# power.net
KiCad netlist of a schematic drawn in EAGLE
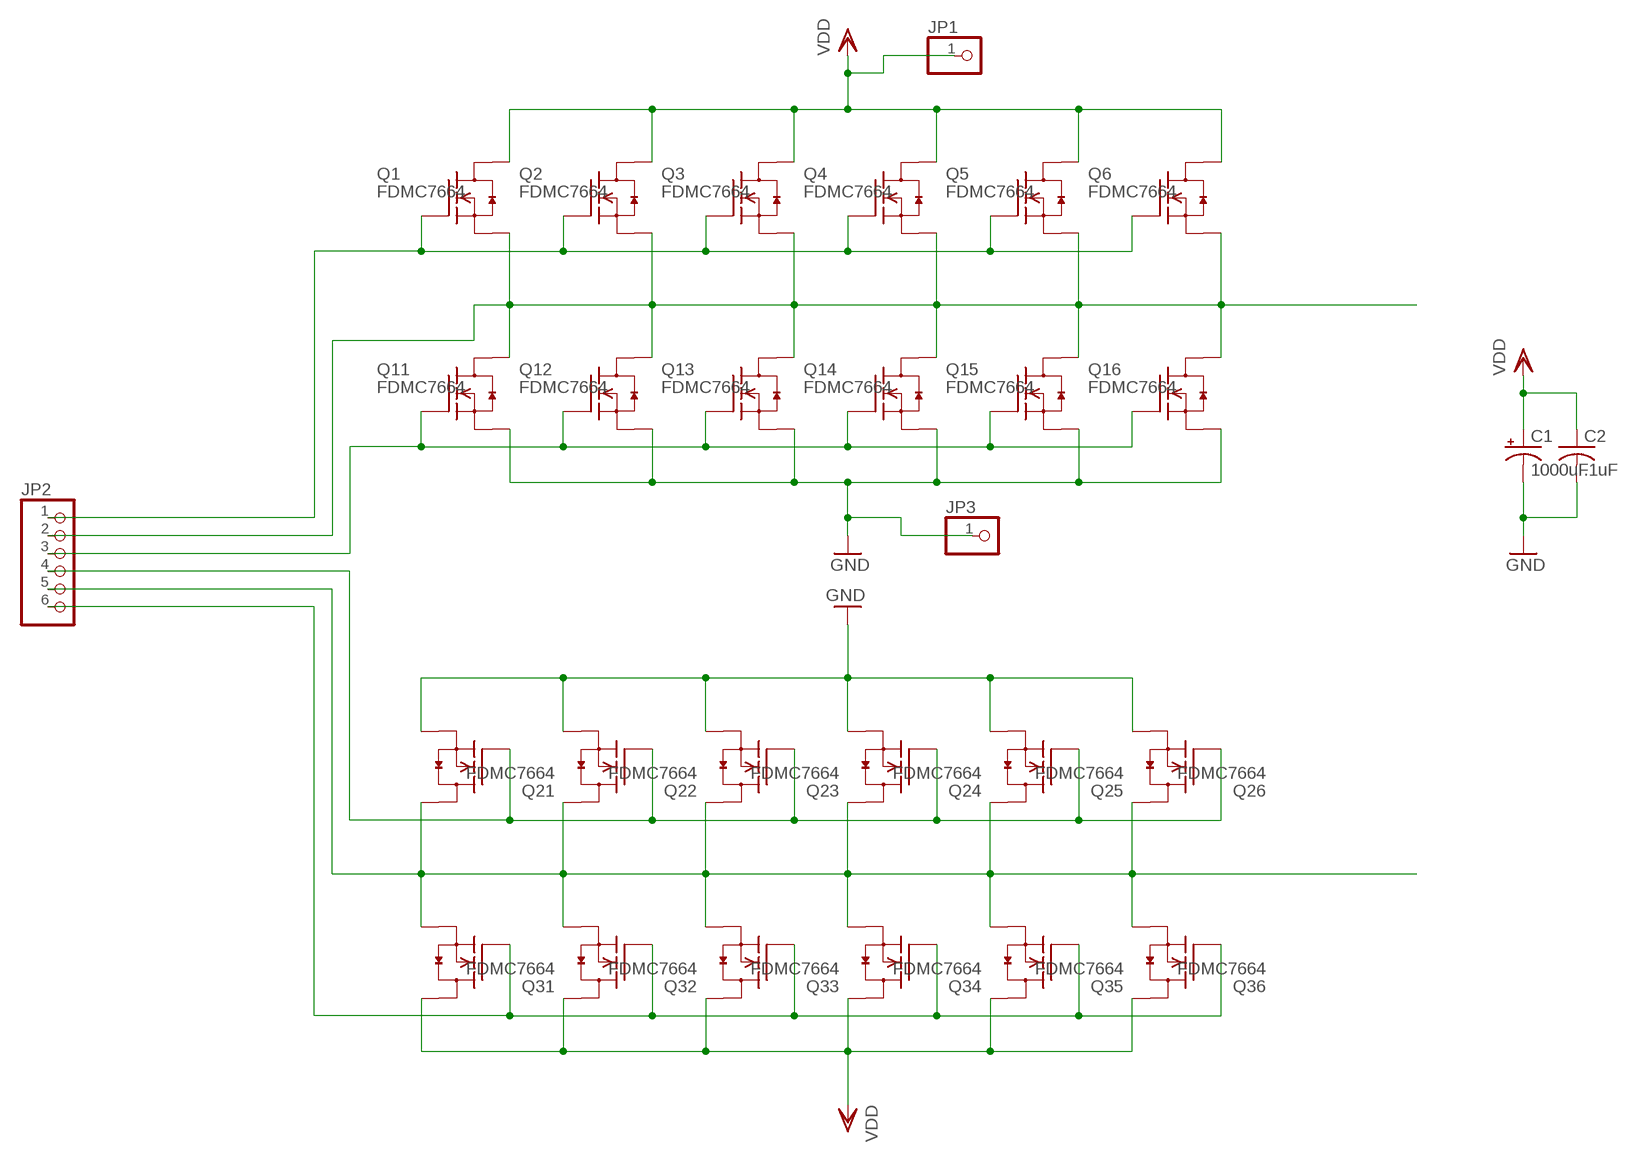
[diagram p0: schematic, sheet 1]

(export (version "E")
  (design (tool "Eeschema 10.0.6"))
  (components
    (comp (ref "C1")
      (value "1000uF")
      (footprint "eagle-import:140CLH-0810")
      (libsource (lib "eagle-import") (part "CPOL-US140CLH-0810"))
    )
    (comp (ref "C2")
      (value ".1uF")
      (footprint "eagle-import:C0603")
      (libsource (lib "eagle-import") (part "C-USC0603"))
    )
    (comp (ref "JP1")
      (value "PINHD-1X1")
      (footprint "eagle-import:1X01")
      (libsource (lib "eagle-import") (part "PINHD-1X1"))
    )
    (comp (ref "JP2")
      (value "PINHD-1X6")
      (footprint "eagle-import:1X06")
      (libsource (lib "eagle-import") (part "PINHD-1X6"))
    )
    (comp (ref "JP3")
      (value "PINHD-1X1")
      (footprint "eagle-import:1X01")
      (libsource (lib "eagle-import") (part "PINHD-1X1"))
    )
    (comp (ref "Q1")
      (value "FDMC7664")
      (footprint "eagle-import:MLP33")
      (libsource (lib "eagle-import") (part "FDMC7664"))
    )
    (comp (ref "Q2")
      (value "FDMC7664")
      (footprint "eagle-import:MLP33")
      (libsource (lib "eagle-import") (part "FDMC7664"))
    )
    (comp (ref "Q3")
      (value "FDMC7664")
      (footprint "eagle-import:MLP33")
      (libsource (lib "eagle-import") (part "FDMC7664"))
    )
    (comp (ref "Q4")
      (value "FDMC7664")
      (footprint "eagle-import:MLP33")
      (libsource (lib "eagle-import") (part "FDMC7664"))
    )
    (comp (ref "Q5")
      (value "FDMC7664")
      (footprint "eagle-import:MLP33")
      (libsource (lib "eagle-import") (part "FDMC7664"))
    )
    (comp (ref "Q6")
      (value "FDMC7664")
      (footprint "eagle-import:MLP33")
      (libsource (lib "eagle-import") (part "FDMC7664"))
    )
    (comp (ref "Q11")
      (value "FDMC7664")
      (footprint "eagle-import:MLP33")
      (libsource (lib "eagle-import") (part "FDMC7664"))
    )
    (comp (ref "Q12")
      (value "FDMC7664")
      (footprint "eagle-import:MLP33")
      (libsource (lib "eagle-import") (part "FDMC7664"))
    )
    (comp (ref "Q13")
      (value "FDMC7664")
      (footprint "eagle-import:MLP33")
      (libsource (lib "eagle-import") (part "FDMC7664"))
    )
    (comp (ref "Q14")
      (value "FDMC7664")
      (footprint "eagle-import:MLP33")
      (libsource (lib "eagle-import") (part "FDMC7664"))
    )
    (comp (ref "Q15")
      (value "FDMC7664")
      (footprint "eagle-import:MLP33")
      (libsource (lib "eagle-import") (part "FDMC7664"))
    )
    (comp (ref "Q16")
      (value "FDMC7664")
      (footprint "eagle-import:MLP33")
      (libsource (lib "eagle-import") (part "FDMC7664"))
    )
    (comp (ref "Q21")
      (value "FDMC7664")
      (footprint "eagle-import:MLP33")
      (libsource (lib "eagle-import") (part "FDMC7664"))
    )
    (comp (ref "Q22")
      (value "FDMC7664")
      (footprint "eagle-import:MLP33")
      (libsource (lib "eagle-import") (part "FDMC7664"))
    )
    (comp (ref "Q23")
      (value "FDMC7664")
      (footprint "eagle-import:MLP33")
      (libsource (lib "eagle-import") (part "FDMC7664"))
    )
    (comp (ref "Q24")
      (value "FDMC7664")
      (footprint "eagle-import:MLP33")
      (libsource (lib "eagle-import") (part "FDMC7664"))
    )
    (comp (ref "Q25")
      (value "FDMC7664")
      (footprint "eagle-import:MLP33")
      (libsource (lib "eagle-import") (part "FDMC7664"))
    )
    (comp (ref "Q26")
      (value "FDMC7664")
      (footprint "eagle-import:MLP33")
      (libsource (lib "eagle-import") (part "FDMC7664"))
    )
    (comp (ref "Q31")
      (value "FDMC7664")
      (footprint "eagle-import:MLP33")
      (libsource (lib "eagle-import") (part "FDMC7664"))
    )
    (comp (ref "Q32")
      (value "FDMC7664")
      (footprint "eagle-import:MLP33")
      (libsource (lib "eagle-import") (part "FDMC7664"))
    )
    (comp (ref "Q33")
      (value "FDMC7664")
      (footprint "eagle-import:MLP33")
      (libsource (lib "eagle-import") (part "FDMC7664"))
    )
    (comp (ref "Q34")
      (value "FDMC7664")
      (footprint "eagle-import:MLP33")
      (libsource (lib "eagle-import") (part "FDMC7664"))
    )
    (comp (ref "Q35")
      (value "FDMC7664")
      (footprint "eagle-import:MLP33")
      (libsource (lib "eagle-import") (part "FDMC7664"))
    )
    (comp (ref "Q36")
      (value "FDMC7664")
      (footprint "eagle-import:MLP33")
      (libsource (lib "eagle-import") (part "FDMC7664"))
    )
  )
  (nets
    (net (code "1") (name "GND") (class "Default")
      (node (ref "C1") (pin "-") (pinfunction "-_-") (pintype "passive"))
      (node (ref "C2") (pin "2") (pinfunction "2_2") (pintype "passive"))
      (node (ref "JP3") (pin "1") (pinfunction "1_1") (pintype "passive"))
      (node (ref "Q11") (pin "123S") (pinfunction "S_123S") (pintype "passive"))
      (node (ref "Q12") (pin "123S") (pinfunction "S_123S") (pintype "passive"))
      (node (ref "Q13") (pin "123S") (pinfunction "S_123S") (pintype "passive"))
      (node (ref "Q14") (pin "123S") (pinfunction "S_123S") (pintype "passive"))
      (node (ref "Q15") (pin "123S") (pinfunction "S_123S") (pintype "passive"))
      (node (ref "Q16") (pin "123S") (pinfunction "S_123S") (pintype "passive"))
      (node (ref "Q21") (pin "123S") (pinfunction "S_123S") (pintype "passive"))
      (node (ref "Q22") (pin "123S") (pinfunction "S_123S") (pintype "passive"))
      (node (ref "Q23") (pin "123S") (pinfunction "S_123S") (pintype "passive"))
      (node (ref "Q24") (pin "123S") (pinfunction "S_123S") (pintype "passive"))
      (node (ref "Q25") (pin "123S") (pinfunction "S_123S") (pintype "passive"))
      (node (ref "Q26") (pin "123S") (pinfunction "S_123S") (pintype "passive"))
    )
    (net (code "2") (name "Net-(Q1-G)") (class "Default")
      (node (ref "JP2") (pin "1") (pinfunction "1_1") (pintype "passive"))
      (node (ref "Q1") (pin "4G") (pinfunction "G_4G") (pintype "passive"))
      (node (ref "Q2") (pin "4G") (pinfunction "G_4G") (pintype "passive"))
      (node (ref "Q3") (pin "4G") (pinfunction "G_4G") (pintype "passive"))
      (node (ref "Q4") (pin "4G") (pinfunction "G_4G") (pintype "passive"))
      (node (ref "Q5") (pin "4G") (pinfunction "G_4G") (pintype "passive"))
      (node (ref "Q6") (pin "4G") (pinfunction "G_4G") (pintype "passive"))
    )
    (net (code "3") (name "Net-(Q1-S)") (class "Default")
      (node (ref "JP2") (pin "2") (pinfunction "2_2") (pintype "passive"))
      (node (ref "Q1") (pin "123S") (pinfunction "S_123S") (pintype "passive"))
      (node (ref "Q11") (pin "5678D") (pinfunction "D_5678D") (pintype "passive"))
      (node (ref "Q12") (pin "5678D") (pinfunction "D_5678D") (pintype "passive"))
      (node (ref "Q13") (pin "5678D") (pinfunction "D_5678D") (pintype "passive"))
      (node (ref "Q14") (pin "5678D") (pinfunction "D_5678D") (pintype "passive"))
      (node (ref "Q15") (pin "5678D") (pinfunction "D_5678D") (pintype "passive"))
      (node (ref "Q16") (pin "5678D") (pinfunction "D_5678D") (pintype "passive"))
      (node (ref "Q2") (pin "123S") (pinfunction "S_123S") (pintype "passive"))
      (node (ref "Q3") (pin "123S") (pinfunction "S_123S") (pintype "passive"))
      (node (ref "Q4") (pin "123S") (pinfunction "S_123S") (pintype "passive"))
      (node (ref "Q5") (pin "123S") (pinfunction "S_123S") (pintype "passive"))
      (node (ref "Q6") (pin "123S") (pinfunction "S_123S") (pintype "passive"))
    )
    (net (code "4") (name "Net-(Q11-G)") (class "Default")
      (node (ref "JP2") (pin "3") (pinfunction "3_3") (pintype "passive"))
      (node (ref "Q11") (pin "4G") (pinfunction "G_4G") (pintype "passive"))
      (node (ref "Q12") (pin "4G") (pinfunction "G_4G") (pintype "passive"))
      (node (ref "Q13") (pin "4G") (pinfunction "G_4G") (pintype "passive"))
      (node (ref "Q14") (pin "4G") (pinfunction "G_4G") (pintype "passive"))
      (node (ref "Q15") (pin "4G") (pinfunction "G_4G") (pintype "passive"))
      (node (ref "Q16") (pin "4G") (pinfunction "G_4G") (pintype "passive"))
    )
    (net (code "5") (name "Net-(Q21-D)") (class "Default")
      (node (ref "JP2") (pin "5") (pinfunction "5_5") (pintype "passive"))
      (node (ref "Q21") (pin "5678D") (pinfunction "D_5678D") (pintype "passive"))
      (node (ref "Q22") (pin "5678D") (pinfunction "D_5678D") (pintype "passive"))
      (node (ref "Q23") (pin "5678D") (pinfunction "D_5678D") (pintype "passive"))
      (node (ref "Q24") (pin "5678D") (pinfunction "D_5678D") (pintype "passive"))
      (node (ref "Q25") (pin "5678D") (pinfunction "D_5678D") (pintype "passive"))
      (node (ref "Q26") (pin "5678D") (pinfunction "D_5678D") (pintype "passive"))
      (node (ref "Q31") (pin "123S") (pinfunction "S_123S") (pintype "passive"))
      (node (ref "Q32") (pin "123S") (pinfunction "S_123S") (pintype "passive"))
      (node (ref "Q33") (pin "123S") (pinfunction "S_123S") (pintype "passive"))
      (node (ref "Q34") (pin "123S") (pinfunction "S_123S") (pintype "passive"))
      (node (ref "Q35") (pin "123S") (pinfunction "S_123S") (pintype "passive"))
      (node (ref "Q36") (pin "123S") (pinfunction "S_123S") (pintype "passive"))
    )
    (net (code "6") (name "Net-(Q21-G)") (class "Default")
      (node (ref "JP2") (pin "4") (pinfunction "4_4") (pintype "passive"))
      (node (ref "Q21") (pin "4G") (pinfunction "G_4G") (pintype "passive"))
      (node (ref "Q22") (pin "4G") (pinfunction "G_4G") (pintype "passive"))
      (node (ref "Q23") (pin "4G") (pinfunction "G_4G") (pintype "passive"))
      (node (ref "Q24") (pin "4G") (pinfunction "G_4G") (pintype "passive"))
      (node (ref "Q25") (pin "4G") (pinfunction "G_4G") (pintype "passive"))
      (node (ref "Q26") (pin "4G") (pinfunction "G_4G") (pintype "passive"))
    )
    (net (code "7") (name "Net-(Q31-G)") (class "Default")
      (node (ref "JP2") (pin "6") (pinfunction "6_6") (pintype "passive"))
      (node (ref "Q31") (pin "4G") (pinfunction "G_4G") (pintype "passive"))
      (node (ref "Q32") (pin "4G") (pinfunction "G_4G") (pintype "passive"))
      (node (ref "Q33") (pin "4G") (pinfunction "G_4G") (pintype "passive"))
      (node (ref "Q34") (pin "4G") (pinfunction "G_4G") (pintype "passive"))
      (node (ref "Q35") (pin "4G") (pinfunction "G_4G") (pintype "passive"))
      (node (ref "Q36") (pin "4G") (pinfunction "G_4G") (pintype "passive"))
    )
    (net (code "8") (name "VDD") (class "Default")
      (node (ref "C1") (pin "+") (pinfunction "+_+") (pintype "passive"))
      (node (ref "C2") (pin "1") (pinfunction "1_1") (pintype "passive"))
      (node (ref "JP1") (pin "1") (pinfunction "1_1") (pintype "passive"))
      (node (ref "Q1") (pin "5678D") (pinfunction "D_5678D") (pintype "passive"))
      (node (ref "Q2") (pin "5678D") (pinfunction "D_5678D") (pintype "passive"))
      (node (ref "Q3") (pin "5678D") (pinfunction "D_5678D") (pintype "passive"))
      (node (ref "Q31") (pin "5678D") (pinfunction "D_5678D") (pintype "passive"))
      (node (ref "Q32") (pin "5678D") (pinfunction "D_5678D") (pintype "passive"))
      (node (ref "Q33") (pin "5678D") (pinfunction "D_5678D") (pintype "passive"))
      (node (ref "Q34") (pin "5678D") (pinfunction "D_5678D") (pintype "passive"))
      (node (ref "Q35") (pin "5678D") (pinfunction "D_5678D") (pintype "passive"))
      (node (ref "Q36") (pin "5678D") (pinfunction "D_5678D") (pintype "passive"))
      (node (ref "Q4") (pin "5678D") (pinfunction "D_5678D") (pintype "passive"))
      (node (ref "Q5") (pin "5678D") (pinfunction "D_5678D") (pintype "passive"))
      (node (ref "Q6") (pin "5678D") (pinfunction "D_5678D") (pintype "passive"))
    )
  )
)
